# numitron_tube_clock.net
KiCad netlist of a schematic drawn in EAGLE
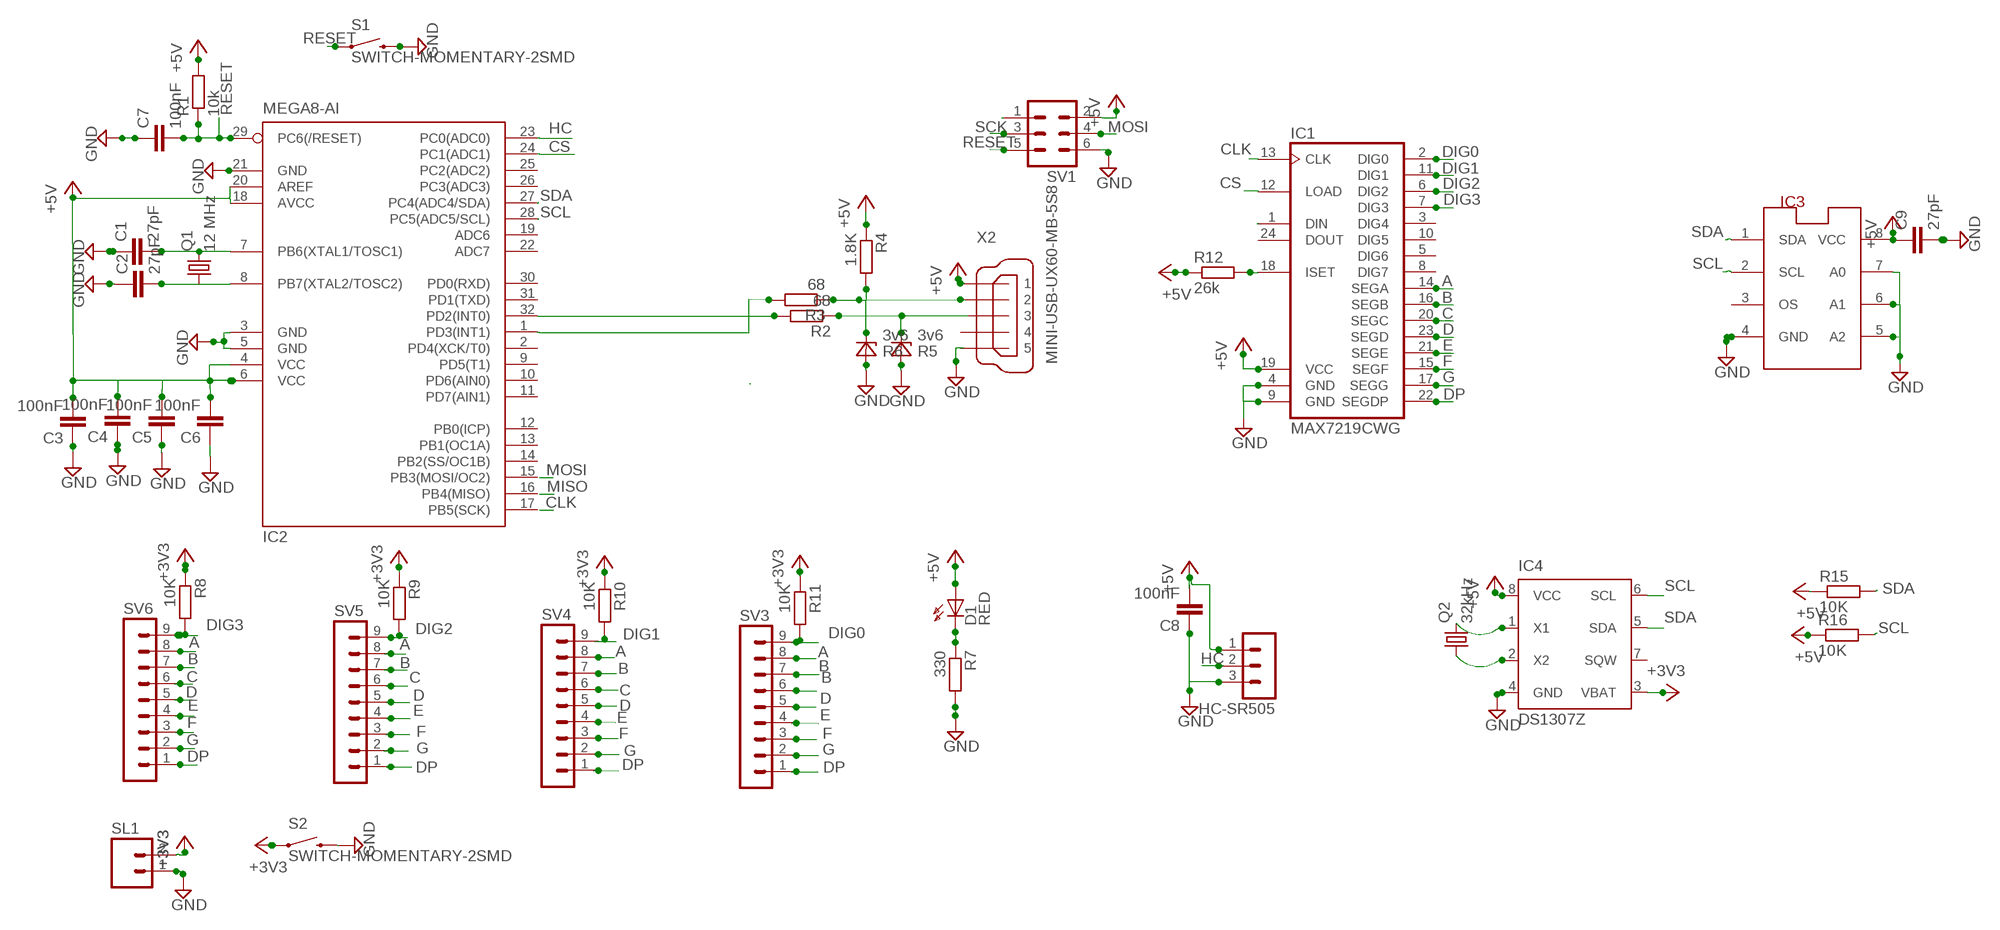
[diagram p0: schematic, sheet 1]

(export (version "E")
  (design (tool "Eeschema 10.0.6"))
  (components
    (comp (ref "C1")
      (value "27pF")
      (footprint "eagle-import:C0805")
      (libsource (lib "eagle-import") (part "C-EUC0805"))
    )
    (comp (ref "C2")
      (value "27pF")
      (footprint "eagle-import:C0805")
      (libsource (lib "eagle-import") (part "C-EUC0805"))
    )
    (comp (ref "C3")
      (value "100nF")
      (footprint "eagle-import:C0805")
      (libsource (lib "eagle-import") (part "C-EUC0805"))
    )
    (comp (ref "C4")
      (value "100nF")
      (footprint "eagle-import:C0805")
      (libsource (lib "eagle-import") (part "C-EUC0805"))
    )
    (comp (ref "C5")
      (value "100nF")
      (footprint "eagle-import:C0805")
      (libsource (lib "eagle-import") (part "C-EUC0805"))
    )
    (comp (ref "C6")
      (value "100nF")
      (footprint "eagle-import:C0805")
      (libsource (lib "eagle-import") (part "C-EUC0805"))
    )
    (comp (ref "C7")
      (value "100nF")
      (footprint "eagle-import:C0805")
      (libsource (lib "eagle-import") (part "C-EUC0805"))
    )
    (comp (ref "C8")
      (value "100nF")
      (footprint "eagle-import:C0805")
      (libsource (lib "eagle-import") (part "C-EUC0805"))
    )
    (comp (ref "C9")
      (value "27pF")
      (footprint "eagle-import:C0805")
      (libsource (lib "eagle-import") (part "C-EUC0805"))
    )
    (comp (ref "D1")
      (value "RED")
      (footprint "eagle-import:HLMP6")
      (fields (field (name "MF") "AGILENT TECHNOLOGIES") (field (name "MPN") "HLMP-6500"))
      (libsource (lib "eagle-import") (part "HLMP6"))
    )
    (comp (ref "HC-SR505")
      (value "MA03-1")
      (footprint "eagle-import:MA03-1")
      (libsource (lib "eagle-import") (part "MA03-1"))
    )
    (comp (ref "IC1")
      (value "MAX7219CWG")
      (footprint "eagle-import:SO24L")
      (libsource (lib "eagle-import") (part "MAX7219CWG"))
    )
    (comp (ref "IC2")
      (value "MEGA8-AI")
      (footprint "eagle-import:TQFP32-08")
      (fields (field (name "MPN") "ATMEGA8-16AU"))
      (libsource (lib "eagle-import") (part "MEGA8-AI"))
    )
    (comp (ref "IC3")
      (value "LM75_ICN")
      (footprint "eagle-import:SO8_LM75")
      (libsource (lib "eagle-import") (part "LM75_ICN"))
    )
    (comp (ref "IC4")
      (value "DS1307Z")
      (footprint "eagle-import:SOIC8")
      (libsource (lib "eagle-import") (part "DS1307Z"))
    )
    (comp (ref "Q1")
      (value "12 MHz")
      (footprint "eagle-import:HC49U-V")
      (libsource (lib "eagle-import") (part "CRYSTALHC49U-V"))
    )
    (comp (ref "Q2")
      (value "32kHz")
      (footprint "eagle-import:HC49U-V")
      (libsource (lib "eagle-import") (part "CRYSTALHC49U-V"))
    )
    (comp (ref "R1")
      (value "10k")
      (footprint "eagle-import:M0805")
      (libsource (lib "eagle-import") (part "R-EU_M0805"))
    )
    (comp (ref "R2")
      (value "68")
      (footprint "eagle-import:M0805")
      (libsource (lib "eagle-import") (part "R-EU_M0805"))
    )
    (comp (ref "R3")
      (value "68")
      (footprint "eagle-import:M0805")
      (libsource (lib "eagle-import") (part "R-EU_M0805"))
    )
    (comp (ref "R4")
      (value "1.8K")
      (footprint "eagle-import:M0805")
      (libsource (lib "eagle-import") (part "R-EU_M0805"))
    )
    (comp (ref "R5")
      (value "3v6")
      (footprint "eagle-import:Z-DIODE")
      (libsource (lib "eagle-import") (part "Z-DIODE"))
    )
    (comp (ref "R6")
      (value "3v6")
      (footprint "eagle-import:Z-DIODE")
      (libsource (lib "eagle-import") (part "Z-DIODE"))
    )
    (comp (ref "R7")
      (value "330")
      (footprint "eagle-import:M0805")
      (libsource (lib "eagle-import") (part "R-EU_M0805"))
    )
    (comp (ref "R8")
      (value "10K")
      (footprint "eagle-import:M0805")
      (libsource (lib "eagle-import") (part "R-EU_M0805"))
    )
    (comp (ref "R9")
      (value "10K")
      (footprint "eagle-import:M0805")
      (libsource (lib "eagle-import") (part "R-EU_M0805"))
    )
    (comp (ref "R10")
      (value "10K")
      (footprint "eagle-import:M0805")
      (libsource (lib "eagle-import") (part "R-EU_M0805"))
    )
    (comp (ref "R11")
      (value "10K")
      (footprint "eagle-import:M0805")
      (libsource (lib "eagle-import") (part "R-EU_M0805"))
    )
    (comp (ref "R12")
      (value "26k")
      (footprint "eagle-import:M0805")
      (libsource (lib "eagle-import") (part "R-EU_M0805"))
    )
    (comp (ref "R15")
      (value "10K")
      (footprint "eagle-import:M0805")
      (libsource (lib "eagle-import") (part "R-EU_M0805"))
    )
    (comp (ref "R16")
      (value "10K")
      (footprint "eagle-import:M0805")
      (libsource (lib "eagle-import") (part "R-EU_M0805"))
    )
    (comp (ref "S1")
      (value "SWITCH-MOMENTARY-2SMD")
      (footprint "eagle-import:TACTILE-SWITCH-SMD")
      (libsource (lib "eagle-import") (part "SWITCH-MOMENTARY-2SMD"))
    )
    (comp (ref "S2")
      (value "SWITCH-MOMENTARY-2SMD")
      (footprint "eagle-import:TACTILE-SWITCH-SMD")
      (libsource (lib "eagle-import") (part "SWITCH-MOMENTARY-2SMD"))
    )
    (comp (ref "SL1")
      (value "MA02")
      (footprint "eagle-import:02PA")
      (libsource (lib "eagle-import") (part "MA02"))
    )
    (comp (ref "SV1")
      (value "MA03-2")
      (footprint "eagle-import:MA03-2")
      (libsource (lib "eagle-import") (part "MA03-2"))
    )
    (comp (ref "SV3")
      (value "MA09-1")
      (footprint "eagle-import:MA09-1")
      (libsource (lib "eagle-import") (part "MA09-1"))
    )
    (comp (ref "SV4")
      (value "MA09-1")
      (footprint "eagle-import:MA09-1")
      (libsource (lib "eagle-import") (part "MA09-1"))
    )
    (comp (ref "SV5")
      (value "MA09-1")
      (footprint "eagle-import:MA09-1")
      (libsource (lib "eagle-import") (part "MA09-1"))
    )
    (comp (ref "SV6")
      (value "MA09-1")
      (footprint "eagle-import:MA09-1")
      (libsource (lib "eagle-import") (part "MA09-1"))
    )
    (comp (ref "X2")
      (value "MINI-USB-UX60-MB-5S8")
      (footprint "eagle-import:UX60-MB-5S8")
      (libsource (lib "eagle-import") (part "MINI-USB-UX60-MB-5S8"))
    )
  )
  (nets
    (net (code "1") (name "+3V3") (class "Default")
      (node (ref "IC4") (pin "3") (pinfunction "VBAT_3") (pintype "passive"))
      (node (ref "R11") (pin "1") (pinfunction "1_1") (pintype "passive"))
      (node (ref "S2") (pin "1") (pinfunction "1_1") (pintype "passive"))
    )
    (net (code "2") (name "+5V") (class "Default")
      (node (ref "C3") (pin "2") (pinfunction "2_2") (pintype "passive"))
      (node (ref "C4") (pin "2") (pinfunction "2_2") (pintype "passive"))
      (node (ref "C5") (pin "2") (pinfunction "2_2") (pintype "passive"))
      (node (ref "C6") (pin "2") (pinfunction "2_2") (pintype "passive"))
      (node (ref "C8") (pin "2") (pinfunction "2_2") (pintype "passive"))
      (node (ref "D1") (pin "A") (pinfunction "A_A") (pintype "passive"))
      (node (ref "IC1") (pin "19") (pinfunction "VCC_19") (pintype "power_in"))
      (node (ref "IC2") (pin "18") (pinfunction "AVCC_18") (pintype "power_in"))
      (node (ref "IC2") (pin "20") (pinfunction "AREF_20") (pintype "passive"))
      (node (ref "IC2") (pin "6") (pinfunction "VCC_6") (pintype "power_in"))
      (node (ref "IC4") (pin "8") (pinfunction "VCC_8") (pintype "power_in"))
      (node (ref "R12") (pin "1") (pinfunction "1_1") (pintype "passive"))
      (node (ref "R15") (pin "1") (pinfunction "1_1") (pintype "passive"))
      (node (ref "R16") (pin "1") (pinfunction "1_1") (pintype "passive"))
      (node (ref "R4") (pin "1") (pinfunction "1_1") (pintype "passive"))
      (node (ref "X2") (pin "1") (pinfunction "1_1") (pintype "input"))
    )
    (net (code "3") (name "/A") (class "Default")
      (node (ref "IC1") (pin "14") (pinfunction "SEGA_14") (pintype "output"))
      (node (ref "SV3") (pin "8") (pinfunction "8_8") (pintype "passive"))
      (node (ref "SV4") (pin "8") (pinfunction "8_8") (pintype "passive"))
      (node (ref "SV5") (pin "8") (pinfunction "8_8") (pintype "passive"))
      (node (ref "SV6") (pin "8") (pinfunction "8_8") (pintype "passive"))
    )
    (net (code "4") (name "/B") (class "Default")
      (node (ref "IC1") (pin "16") (pinfunction "SEGB_16") (pintype "output"))
      (node (ref "SV3") (pin "7") (pinfunction "7_7") (pintype "passive"))
      (node (ref "SV4") (pin "7") (pinfunction "7_7") (pintype "passive"))
      (node (ref "SV5") (pin "7") (pinfunction "7_7") (pintype "passive"))
      (node (ref "SV6") (pin "7") (pinfunction "7_7") (pintype "passive"))
    )
    (net (code "5") (name "/C") (class "Default")
      (node (ref "IC1") (pin "20") (pinfunction "SEGC_20") (pintype "output"))
      (node (ref "SV4") (pin "6") (pinfunction "6_6") (pintype "passive"))
      (node (ref "SV5") (pin "6") (pinfunction "6_6") (pintype "passive"))
      (node (ref "SV6") (pin "6") (pinfunction "6_6") (pintype "passive"))
    )
    (net (code "6") (name "/CLK") (class "Default")
      (node (ref "IC1") (pin "13") (pinfunction "CLK_13") (pintype "input"))
    )
    (net (code "7") (name "/CS") (class "Default")
      (node (ref "IC1") (pin "12") (pinfunction "LOAD_12") (pintype "input"))
      (node (ref "IC2") (pin "24") (pinfunction "PC1(ADC1)_24") (pintype "bidirectional"))
    )
    (net (code "8") (name "/D") (class "Default")
      (node (ref "IC1") (pin "23") (pinfunction "SEGD_23") (pintype "output"))
      (node (ref "SV3") (pin "5") (pinfunction "5_5") (pintype "passive"))
      (node (ref "SV4") (pin "5") (pinfunction "5_5") (pintype "passive"))
      (node (ref "SV5") (pin "5") (pinfunction "5_5") (pintype "passive"))
      (node (ref "SV6") (pin "5") (pinfunction "5_5") (pintype "passive"))
    )
    (net (code "9") (name "/DIG0") (class "Default")
      (node (ref "IC1") (pin "2") (pinfunction "DIG0_2") (pintype "output"))
      (node (ref "SV3") (pin "9") (pinfunction "9_9") (pintype "passive"))
    )
    (net (code "10") (name "/DIG1") (class "Default")
      (node (ref "IC1") (pin "11") (pinfunction "DIG1_11") (pintype "output"))
    )
    (net (code "11") (name "/DIG2") (class "Default")
      (node (ref "IC1") (pin "6") (pinfunction "DIG2_6") (pintype "output"))
      (node (ref "SV5") (pin "9") (pinfunction "9_9") (pintype "passive"))
    )
    (net (code "12") (name "/DIG3") (class "Default")
      (node (ref "IC1") (pin "7") (pinfunction "DIG3_7") (pintype "output"))
      (node (ref "R8") (pin "2") (pinfunction "2_2") (pintype "passive"))
      (node (ref "SV6") (pin "9") (pinfunction "9_9") (pintype "passive"))
    )
    (net (code "13") (name "/DP") (class "Default")
      (node (ref "IC1") (pin "22") (pinfunction "SEGDP_22") (pintype "output"))
      (node (ref "SV3") (pin "1") (pinfunction "1_1") (pintype "passive"))
      (node (ref "SV4") (pin "1") (pinfunction "1_1") (pintype "passive"))
      (node (ref "SV5") (pin "1") (pinfunction "1_1") (pintype "passive"))
      (node (ref "SV6") (pin "1") (pinfunction "1_1") (pintype "passive"))
    )
    (net (code "14") (name "/E") (class "Default")
      (node (ref "IC1") (pin "21") (pinfunction "SEGE_21") (pintype "output"))
      (node (ref "SV3") (pin "4") (pinfunction "4_4") (pintype "passive"))
      (node (ref "SV4") (pin "4") (pinfunction "4_4") (pintype "passive"))
      (node (ref "SV5") (pin "4") (pinfunction "4_4") (pintype "passive"))
      (node (ref "SV6") (pin "4") (pinfunction "4_4") (pintype "passive"))
    )
    (net (code "15") (name "/F") (class "Default")
      (node (ref "IC1") (pin "15") (pinfunction "SEGF_15") (pintype "output"))
      (node (ref "SV3") (pin "3") (pinfunction "3_3") (pintype "passive"))
      (node (ref "SV4") (pin "3") (pinfunction "3_3") (pintype "passive"))
      (node (ref "SV5") (pin "3") (pinfunction "3_3") (pintype "passive"))
      (node (ref "SV6") (pin "3") (pinfunction "3_3") (pintype "passive"))
    )
    (net (code "16") (name "/G") (class "Default")
      (node (ref "IC1") (pin "17") (pinfunction "SEGG_17") (pintype "output"))
      (node (ref "SV3") (pin "2") (pinfunction "2_2") (pintype "passive"))
      (node (ref "SV4") (pin "2") (pinfunction "2_2") (pintype "passive"))
      (node (ref "SV5") (pin "2") (pinfunction "2_2") (pintype "passive"))
      (node (ref "SV6") (pin "2") (pinfunction "2_2") (pintype "passive"))
    )
    (net (code "17") (name "/HC") (class "Default")
      (node (ref "HC-SR505") (pin "2") (pinfunction "2_2") (pintype "passive"))
      (node (ref "IC2") (pin "23") (pinfunction "PC0(ADC0)_23") (pintype "bidirectional"))
    )
    (net (code "18") (name "/MISO") (class "Default")
      (node (ref "SV1") (pin "1") (pinfunction "1_1") (pintype "passive"))
    )
    (net (code "19") (name "/MOSI") (class "Default")
      (node (ref "IC1") (pin "1") (pinfunction "DIN_1") (pintype "input"))
      (node (ref "SV1") (pin "4") (pinfunction "4_4") (pintype "passive"))
    )
    (net (code "20") (name "/RESET") (class "Default")
      (node (ref "C7") (pin "2") (pinfunction "2_2") (pintype "passive"))
      (node (ref "IC2") (pin "29") (pinfunction "PC6(/RESET)_29") (pintype "bidirectional"))
      (node (ref "SV1") (pin "5") (pinfunction "5_5") (pintype "passive"))
    )
    (net (code "21") (name "/SCK") (class "Default")
      (node (ref "SV1") (pin "3") (pinfunction "3_3") (pintype "passive"))
    )
    (net (code "22") (name "/SCL") (class "Default")
      (node (ref "IC2") (pin "28") (pinfunction "PC5(ADC5/SCL)_28") (pintype "bidirectional"))
      (node (ref "IC3") (pin "2") (pinfunction "SCL_2") (pintype "bidirectional"))
      (node (ref "IC4") (pin "6") (pinfunction "SCL_6") (pintype "input"))
      (node (ref "R16") (pin "2") (pinfunction "2_2") (pintype "passive"))
    )
    (net (code "23") (name "/SDA") (class "Default")
      (node (ref "IC2") (pin "27") (pinfunction "PC4(ADC4/SDA)_27") (pintype "bidirectional"))
      (node (ref "IC3") (pin "1") (pinfunction "SDA_1") (pintype "bidirectional"))
      (node (ref "IC4") (pin "5") (pinfunction "SDA_5") (pintype "bidirectional"))
      (node (ref "R15") (pin "2") (pinfunction "2_2") (pintype "passive"))
    )
    (net (code "24") (name "GND") (class "Default")
      (node (ref "C1") (pin "1") (pinfunction "1_1") (pintype "passive"))
      (node (ref "C3") (pin "1") (pinfunction "1_1") (pintype "passive"))
      (node (ref "C4") (pin "1") (pinfunction "1_1") (pintype "passive"))
      (node (ref "C5") (pin "1") (pinfunction "1_1") (pintype "passive"))
      (node (ref "C6") (pin "1") (pinfunction "1_1") (pintype "passive"))
      (node (ref "C7") (pin "1") (pinfunction "1_1") (pintype "passive"))
      (node (ref "C8") (pin "1") (pinfunction "1_1") (pintype "passive"))
      (node (ref "C9") (pin "2") (pinfunction "2_2") (pintype "passive"))
      (node (ref "HC-SR505") (pin "3") (pinfunction "3_3") (pintype "passive"))
      (node (ref "IC2") (pin "21") (pinfunction "GND_21") (pintype "power_in"))
      (node (ref "IC2") (pin "3") (pinfunction "GND_3") (pintype "power_in"))
      (node (ref "IC2") (pin "5") (pinfunction "GND_5") (pintype "power_in"))
      (node (ref "IC3") (pin "6") (pinfunction "A1_6") (pintype "input"))
      (node (ref "IC3") (pin "7") (pinfunction "A0_7") (pintype "input"))
      (node (ref "IC4") (pin "4") (pinfunction "GND_4") (pintype "power_in"))
      (node (ref "R5") (pin "A") (pinfunction "A_A") (pintype "input"))
      (node (ref "R7") (pin "2") (pinfunction "2_2") (pintype "passive"))
      (node (ref "S1") (pin "3") (pinfunction "2_3") (pintype "passive"))
      (node (ref "S2") (pin "3") (pinfunction "2_3") (pintype "passive"))
      (node (ref "SL1") (pin "1") (pinfunction "1_1") (pintype "passive"))
      (node (ref "SV1") (pin "6") (pinfunction "6_6") (pintype "passive"))
    )
    (net (code "25") (name "Net-(C1-Pad2)") (class "Default")
      (node (ref "C1") (pin "2") (pinfunction "2_2") (pintype "passive"))
      (node (ref "Q1") (pin "2") (pinfunction "2_2") (pintype "passive"))
    )
    (net (code "26") (name "Net-(C2-Pad2)") (class "Default")
      (node (ref "C2") (pin "2") (pinfunction "2_2") (pintype "passive"))
      (node (ref "Q1") (pin "1") (pinfunction "1_1") (pintype "passive"))
    )
    (net (code "27") (name "Net-(D1-PadK)") (class "Default")
      (node (ref "D1") (pin "K") (pinfunction "K_K") (pintype "passive"))
      (node (ref "R7") (pin "1") (pinfunction "1_1") (pintype "passive"))
    )
    (net (code "28") (name "Net-(IC1-GND-Pad4)") (class "Default")
      (node (ref "IC1") (pin "4") (pinfunction "GND_4") (pintype "power_in"))
      (node (ref "IC1") (pin "9") (pinfunction "GND_9") (pintype "power_in"))
    )
    (net (code "29") (name "Net-(IC1-ISET)") (class "Default")
      (node (ref "IC1") (pin "18") (pinfunction "ISET_18") (pintype "input"))
      (node (ref "R12") (pin "2") (pinfunction "2_2") (pintype "passive"))
    )
    (net (code "30") (name "Net-(IC2-PD2(INT0))") (class "Default")
      (node (ref "IC2") (pin "32") (pinfunction "PD2(INT0)_32") (pintype "bidirectional"))
      (node (ref "R2") (pin "2") (pinfunction "2_2") (pintype "passive"))
    )
    (net (code "31") (name "Net-(IC3-VCC)") (class "Default")
      (node (ref "C9") (pin "1") (pinfunction "1_1") (pintype "passive"))
      (node (ref "IC3") (pin "8") (pinfunction "VCC_8") (pintype "power_in"))
    )
    (net (code "32") (name "Net-(IC4-X1)") (class "Default")
      (node (ref "IC4") (pin "1") (pinfunction "X1_1") (pintype "input"))
      (node (ref "Q2") (pin "2") (pinfunction "2_2") (pintype "passive"))
    )
    (net (code "33") (name "Net-(IC4-X2)") (class "Default")
      (node (ref "IC4") (pin "2") (pinfunction "X2_2") (pintype "output"))
      (node (ref "Q2") (pin "1") (pinfunction "1_1") (pintype "passive"))
    )
    (net (code "34") (name "Net-(R2-Pad1)") (class "Default")
      (node (ref "R2") (pin "1") (pinfunction "1_1") (pintype "passive"))
      (node (ref "X2") (pin "3") (pinfunction "3_3") (pintype "input"))
    )
    (net (code "35") (name "Net-(R3-Pad1)") (class "Default")
      (node (ref "R3") (pin "1") (pinfunction "1_1") (pintype "passive"))
      (node (ref "R4") (pin "2") (pinfunction "2_2") (pintype "passive"))
      (node (ref "X2") (pin "2") (pinfunction "2_2") (pintype "input"))
    )
    (net (code "36") (name "unconnected-(C2-Pad1)") (class "Default")
      (node (ref "C2") (pin "1") (pinfunction "1_1") (pintype "passive"))
    )
    (net (code "37") (name "unconnected-(HC-SR505-Pad1)") (class "Default")
      (node (ref "HC-SR505") (pin "1") (pinfunction "1_1") (pintype "passive"))
    )
    (net (code "38") (name "unconnected-(IC1-DIG4-Pad3)") (class "Default")
      (node (ref "IC1") (pin "3") (pinfunction "DIG4_3") (pintype "output"))
    )
    (net (code "39") (name "unconnected-(IC1-DIG5-Pad10)") (class "Default")
      (node (ref "IC1") (pin "10") (pinfunction "DIG5_10") (pintype "output"))
    )
    (net (code "40") (name "unconnected-(IC1-DIG6-Pad5)") (class "Default")
      (node (ref "IC1") (pin "5") (pinfunction "DIG6_5") (pintype "output"))
    )
    (net (code "41") (name "unconnected-(IC1-DIG7-Pad8)") (class "Default")
      (node (ref "IC1") (pin "8") (pinfunction "DIG7_8") (pintype "output"))
    )
    (net (code "42") (name "unconnected-(IC1-DOUT-Pad24)") (class "Default")
      (node (ref "IC1") (pin "24") (pinfunction "DOUT_24") (pintype "output"))
    )
    (net (code "43") (name "unconnected-(IC2-ADC6-Pad19)") (class "Default")
      (node (ref "IC2") (pin "19") (pinfunction "ADC6_19") (pintype "bidirectional"))
    )
    (net (code "44") (name "unconnected-(IC2-ADC7-Pad22)") (class "Default")
      (node (ref "IC2") (pin "22") (pinfunction "ADC7_22") (pintype "bidirectional"))
    )
    (net (code "45") (name "unconnected-(IC2-PB0(ICP)-Pad12)") (class "Default")
      (node (ref "IC2") (pin "12") (pinfunction "PB0(ICP)_12") (pintype "bidirectional"))
    )
    (net (code "46") (name "unconnected-(IC2-PB1(OC1A)-Pad13)") (class "Default")
      (node (ref "IC2") (pin "13") (pinfunction "PB1(OC1A)_13") (pintype "bidirectional"))
    )
    (net (code "47") (name "unconnected-(IC2-PB2(SS{slash}OC1B)-Pad14)") (class "Default")
      (node (ref "IC2") (pin "14") (pinfunction "PB2(SS/OC1B)_14") (pintype "bidirectional"))
    )
    (net (code "48") (name "unconnected-(IC2-PB3(MOSI{slash}OC2)-Pad15)") (class "Default")
      (node (ref "IC2") (pin "15") (pinfunction "PB3(MOSI/OC2)_15") (pintype "bidirectional"))
    )
    (net (code "49") (name "unconnected-(IC2-PB4(MISO)-Pad16)") (class "Default")
      (node (ref "IC2") (pin "16") (pinfunction "PB4(MISO)_16") (pintype "bidirectional"))
    )
    (net (code "50") (name "unconnected-(IC2-PB5(SCK)-Pad17)") (class "Default")
      (node (ref "IC2") (pin "17") (pinfunction "PB5(SCK)_17") (pintype "bidirectional"))
    )
    (net (code "51") (name "unconnected-(IC2-PB6(XTAL1{slash}TOSC1)-Pad7)") (class "Default")
      (node (ref "IC2") (pin "7") (pinfunction "PB6(XTAL1/TOSC1)_7") (pintype "bidirectional"))
    )
    (net (code "52") (name "unconnected-(IC2-PB7(XTAL2{slash}TOSC2)-Pad8)") (class "Default")
      (node (ref "IC2") (pin "8") (pinfunction "PB7(XTAL2/TOSC2)_8") (pintype "bidirectional"))
    )
    (net (code "53") (name "unconnected-(IC2-PC2(ADC2)-Pad25)") (class "Default")
      (node (ref "IC2") (pin "25") (pinfunction "PC2(ADC2)_25") (pintype "bidirectional"))
    )
    (net (code "54") (name "unconnected-(IC2-PC3(ADC3)-Pad26)") (class "Default")
      (node (ref "IC2") (pin "26") (pinfunction "PC3(ADC3)_26") (pintype "bidirectional"))
    )
    (net (code "55") (name "unconnected-(IC2-PD0(RXD)-Pad30)") (class "Default")
      (node (ref "IC2") (pin "30") (pinfunction "PD0(RXD)_30") (pintype "bidirectional"))
    )
    (net (code "56") (name "unconnected-(IC2-PD1(TXD)-Pad31)") (class "Default")
      (node (ref "IC2") (pin "31") (pinfunction "PD1(TXD)_31") (pintype "bidirectional"))
    )
    (net (code "57") (name "unconnected-(IC2-PD3(INT1)-Pad1)") (class "Default")
      (node (ref "IC2") (pin "1") (pinfunction "PD3(INT1)_1") (pintype "bidirectional"))
    )
    (net (code "58") (name "unconnected-(IC2-PD4(XCK{slash}T0)-Pad2)") (class "Default")
      (node (ref "IC2") (pin "2") (pinfunction "PD4(XCK/T0)_2") (pintype "bidirectional"))
    )
    (net (code "59") (name "unconnected-(IC2-PD5(T1)-Pad9)") (class "Default")
      (node (ref "IC2") (pin "9") (pinfunction "PD5(T1)_9") (pintype "bidirectional"))
    )
    (net (code "60") (name "unconnected-(IC2-PD6(AIN0)-Pad10)") (class "Default")
      (node (ref "IC2") (pin "10") (pinfunction "PD6(AIN0)_10") (pintype "bidirectional"))
    )
    (net (code "61") (name "unconnected-(IC2-PD7(AIN1)-Pad11)") (class "Default")
      (node (ref "IC2") (pin "11") (pinfunction "PD7(AIN1)_11") (pintype "bidirectional"))
    )
    (net (code "62") (name "unconnected-(IC2-VCC-Pad4)") (class "Default")
      (node (ref "IC2") (pin "4") (pinfunction "VCC_4") (pintype "power_in"))
    )
    (net (code "63") (name "unconnected-(IC3-A2-Pad5)") (class "Default")
      (node (ref "IC3") (pin "5") (pinfunction "A2_5") (pintype "input"))
    )
    (net (code "64") (name "unconnected-(IC3-GND-Pad4)") (class "Default")
      (node (ref "IC3") (pin "4") (pinfunction "GND_4") (pintype "power_in"))
    )
    (net (code "65") (name "unconnected-(IC3-OS-Pad3)") (class "Default")
      (node (ref "IC3") (pin "3") (pinfunction "OS_3") (pintype "output"))
    )
    (net (code "66") (name "unconnected-(IC4-SQW-Pad7)") (class "Default")
      (node (ref "IC4") (pin "7") (pinfunction "SQW_7") (pintype "open_collector"))
    )
    (net (code "67") (name "unconnected-(R1-Pad1)") (class "Default")
      (node (ref "R1") (pin "1") (pinfunction "1_1") (pintype "passive"))
    )
    (net (code "68") (name "unconnected-(R1-Pad2)") (class "Default")
      (node (ref "R1") (pin "2") (pinfunction "2_2") (pintype "passive"))
    )
    (net (code "69") (name "unconnected-(R3-Pad2)") (class "Default")
      (node (ref "R3") (pin "2") (pinfunction "2_2") (pintype "passive"))
    )
    (net (code "70") (name "unconnected-(R5-PadC)") (class "Default")
      (node (ref "R5") (pin "C") (pinfunction "C_C") (pintype "input"))
    )
    (net (code "71") (name "unconnected-(R6-PadA)") (class "Default")
      (node (ref "R6") (pin "A") (pinfunction "A_A") (pintype "input"))
    )
    (net (code "72") (name "unconnected-(R6-PadC)") (class "Default")
      (node (ref "R6") (pin "C") (pinfunction "C_C") (pintype "input"))
    )
    (net (code "73") (name "unconnected-(R8-Pad1)") (class "Default")
      (node (ref "R8") (pin "1") (pinfunction "1_1") (pintype "passive"))
    )
    (net (code "74") (name "unconnected-(R9-Pad1)") (class "Default")
      (node (ref "R9") (pin "1") (pinfunction "1_1") (pintype "passive"))
    )
    (net (code "75") (name "unconnected-(R9-Pad2)") (class "Default")
      (node (ref "R9") (pin "2") (pinfunction "2_2") (pintype "passive"))
    )
    (net (code "76") (name "unconnected-(R10-Pad1)") (class "Default")
      (node (ref "R10") (pin "1") (pinfunction "1_1") (pintype "passive"))
    )
    (net (code "77") (name "unconnected-(R10-Pad2)") (class "Default")
      (node (ref "R10") (pin "2") (pinfunction "2_2") (pintype "passive"))
    )
    (net (code "78") (name "unconnected-(R11-Pad2)") (class "Default")
      (node (ref "R11") (pin "2") (pinfunction "2_2") (pintype "passive"))
    )
    (net (code "79") (name "unconnected-(S1-Pad1)") (class "Default")
      (node (ref "S1") (pin "1") (pinfunction "1_1") (pintype "passive"))
    )
    (net (code "80") (name "unconnected-(SL1-Pad2)") (class "Default")
      (node (ref "SL1") (pin "2") (pinfunction "2_2") (pintype "passive"))
    )
    (net (code "81") (name "unconnected-(SV1-Pad2)") (class "Default")
      (node (ref "SV1") (pin "2") (pinfunction "2_2") (pintype "passive"))
    )
    (net (code "82") (name "unconnected-(SV3-Pad6)") (class "Default")
      (node (ref "SV3") (pin "6") (pinfunction "6_6") (pintype "passive"))
    )
    (net (code "83") (name "unconnected-(SV4-Pad9)") (class "Default")
      (node (ref "SV4") (pin "9") (pinfunction "9_9") (pintype "passive"))
    )
    (net (code "84") (name "unconnected-(X2-Pad4)") (class "Default")
      (node (ref "X2") (pin "4") (pinfunction "4_4") (pintype "input"))
    )
    (net (code "85") (name "unconnected-(X2-Pad5)") (class "Default")
      (node (ref "X2") (pin "5") (pinfunction "5_5") (pintype "input"))
    )
  )
)
